# POWER_DCDC_SOM.net
KiCad netlist of a schematic drawn in Altium Designer
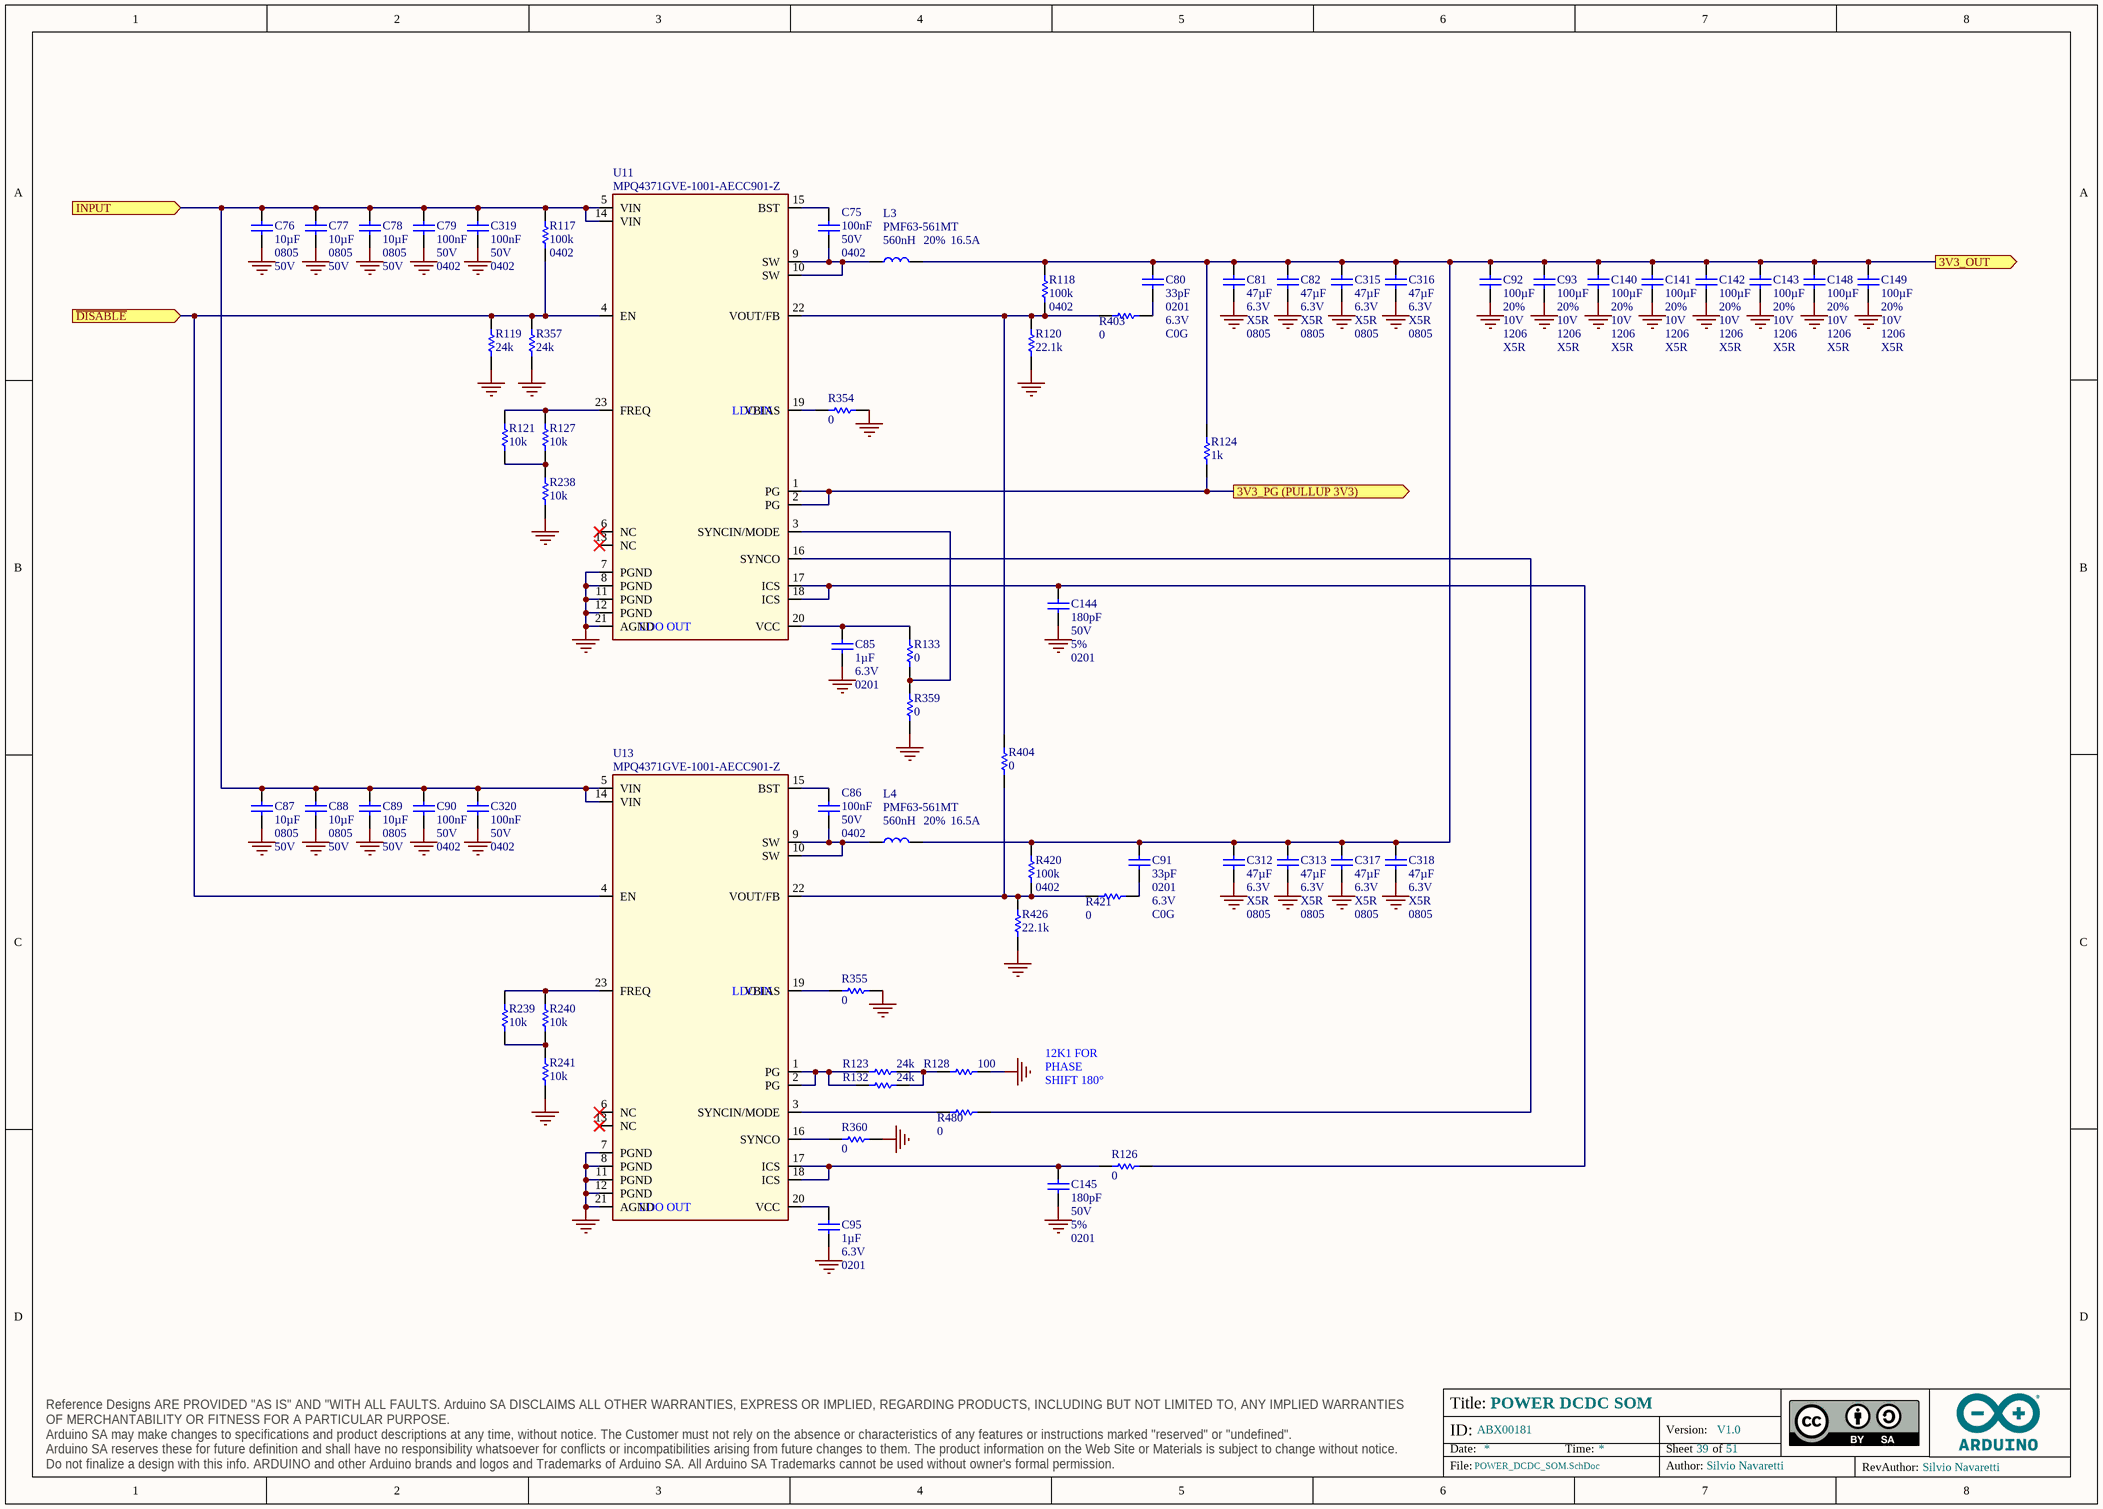
[diagram p0: POWER_DCDC_SOM.SchDoc]

(export (version "E")
  (design (tool "Eeschema 10.0.6"))
  (components
    (comp (ref "C75")
      (value "100nF")
      (footprint "CAP-0402")
      (description "CAP CHIP 0402 100nF 10% 50V X5R")
      (fields
        (field (name "MANUFACTURER") "Murata")
        (field (name "PART NUMBER") "GRM155R61H104KE19D")
        (field (name "VOLTAGE") "50V")
        (field (name "CASE CODE (IMPERIAL)") "0402")
      )
      (libsource (lib "Clean") (part "CAP"))
    )
    (comp (ref "C76")
      (value "10µF")
      (footprint "CAP-0805")
      (description "CAP CHIP 0805 10uF 20% 50V X5R")
      (fields
        (field (name "CASE CODE (IMPERIAL)") "0805")
        (field (name "TOLERANCE") "20%")
        (field (name "PART NUMBER") "GRM21BR61H106ME43L")
        (field (name "VOLTAGE") "50V")
      )
      (libsource (lib "Clean") (part "CAP"))
    )
    (comp (ref "C77")
      (value "10µF")
      (footprint "CAP-0805")
      (description "CAP CHIP 0805 10uF 20% 50V X5R")
      (fields
        (field (name "CASE CODE (IMPERIAL)") "0805")
        (field (name "TOLERANCE") "20%")
        (field (name "PART NUMBER") "GRM21BR61H106ME43L")
        (field (name "VOLTAGE") "50V")
      )
      (libsource (lib "Clean") (part "CAP"))
    )
    (comp (ref "C78")
      (value "10µF")
      (footprint "CAP-0805")
      (description "CAP CHIP 0805 10uF 20% 50V X5R")
      (fields
        (field (name "CASE CODE (IMPERIAL)") "0805")
        (field (name "TOLERANCE") "20%")
        (field (name "PART NUMBER") "GRM21BR61H106ME43L")
        (field (name "VOLTAGE") "50V")
      )
      (libsource (lib "Clean") (part "CAP"))
    )
    (comp (ref "C79")
      (value "100nF")
      (footprint "CAP-0402")
      (description "CAP CHIP 0402 100nF 10% 50V X5R")
      (fields
        (field (name "MANUFACTURER") "Murata")
        (field (name "PART NUMBER") "GRM155R61H104KE19D")
        (field (name "VOLTAGE") "50V")
        (field (name "CASE CODE (IMPERIAL)") "0402")
      )
      (libsource (lib "Clean") (part "CAP"))
    )
    (comp (ref "C80")
      (value "33pF")
      (footprint "CAP-0201")
      (description "CAP CHIP 0201 33pF 5% 6.3V C0G")
      (fields
        (field (name "CASE CODE (IMPERIAL)") "0201")
        (field (name "VOLTAGE") "6.3V")
        (field (name "MANUFACTURER") "Murata Electronics")
        (field (name "DIELECTRIC") "C0G")
        (field (name "TOLERANCE") "5%")
      )
      (libsource (lib "Clean") (part "CAP"))
    )
    (comp (ref "C81")
      (value "47µF")
      (footprint "CAP-0805")
      (description "CAP CHIP 0805 47uF 20% 6.3V X5R")
      (fields
        (field (name "VOLTAGE") "6.3V")
        (field (name "DIELECTRIC") "X5R")
        (field (name "TOLERANCE") "20%")
        (field (name "CASE CODE (IMPERIAL)") "0805")
        (field (name "MANUFACTURER") "KEMET")
      )
      (libsource (lib "Clean") (part "CAP"))
    )
    (comp (ref "C82")
      (value "47µF")
      (footprint "CAP-0805")
      (description "CAP CHIP 0805 47uF 20% 6.3V X5R")
      (fields
        (field (name "VOLTAGE") "6.3V")
        (field (name "DIELECTRIC") "X5R")
        (field (name "TOLERANCE") "20%")
        (field (name "CASE CODE (IMPERIAL)") "0805")
        (field (name "MANUFACTURER") "KEMET")
      )
      (libsource (lib "Clean") (part "CAP"))
    )
    (comp (ref "C85")
      (value "1µF")
      (footprint "CAP-0201")
      (description "CAP CHIP 0201 1uF 20% 6.3V X5R")
      (fields
        (field (name "VOLTAGE") "6.3V")
        (field (name "TOLERANCE") "20%")
        (field (name "PART NUMBER") "GRM033R60J105MEA2D")
        (field (name "CASE CODE (IMPERIAL)") "0201")
      )
      (libsource (lib "Clean") (part "CAP"))
    )
    (comp (ref "C86")
      (value "100nF")
      (footprint "CAP-0402")
      (description "CAP CHIP 0402 100nF 10% 50V X5R")
      (fields
        (field (name "MANUFACTURER") "Murata")
        (field (name "PART NUMBER") "GRM155R61H104KE19D")
        (field (name "VOLTAGE") "50V")
        (field (name "CASE CODE (IMPERIAL)") "0402")
      )
      (libsource (lib "Clean") (part "CAP"))
    )
    (comp (ref "C87")
      (value "10µF")
      (footprint "CAP-0805")
      (description "CAP CHIP 0805 10uF 20% 50V X5R")
      (fields
        (field (name "CASE CODE (IMPERIAL)") "0805")
        (field (name "TOLERANCE") "20%")
        (field (name "PART NUMBER") "GRM21BR61H106ME43L")
        (field (name "VOLTAGE") "50V")
      )
      (libsource (lib "Clean") (part "CAP"))
    )
    (comp (ref "C88")
      (value "10µF")
      (footprint "CAP-0805")
      (description "CAP CHIP 0805 10uF 20% 50V X5R")
      (fields
        (field (name "CASE CODE (IMPERIAL)") "0805")
        (field (name "TOLERANCE") "20%")
        (field (name "PART NUMBER") "GRM21BR61H106ME43L")
        (field (name "VOLTAGE") "50V")
      )
      (libsource (lib "Clean") (part "CAP"))
    )
    (comp (ref "C89")
      (value "10µF")
      (footprint "CAP-0805")
      (description "CAP CHIP 0805 10uF 20% 50V X5R")
      (fields
        (field (name "CASE CODE (IMPERIAL)") "0805")
        (field (name "TOLERANCE") "20%")
        (field (name "PART NUMBER") "GRM21BR61H106ME43L")
        (field (name "VOLTAGE") "50V")
      )
      (libsource (lib "Clean") (part "CAP"))
    )
    (comp (ref "C90")
      (value "100nF")
      (footprint "CAP-0402")
      (description "CAP CHIP 0402 100nF 10% 50V X5R")
      (fields
        (field (name "MANUFACTURER") "Murata")
        (field (name "PART NUMBER") "GRM155R61H104KE19D")
        (field (name "VOLTAGE") "50V")
        (field (name "CASE CODE (IMPERIAL)") "0402")
      )
      (libsource (lib "Clean") (part "CAP"))
    )
    (comp (ref "C91")
      (value "33pF")
      (footprint "CAP-0201")
      (description "CAP CHIP 0201 33pF 5% 6.3V C0G")
      (fields
        (field (name "CASE CODE (IMPERIAL)") "0201")
        (field (name "VOLTAGE") "6.3V")
        (field (name "MANUFACTURER") "Murata Electronics")
        (field (name "DIELECTRIC") "C0G")
        (field (name "TOLERANCE") "5%")
      )
      (libsource (lib "Clean") (part "CAP"))
    )
    (comp (ref "C92")
      (value "100µF")
      (footprint "CAP-1206")
      (description "CAP CHIP 1206 100uF 20% 10V X5R")
      (fields
        (field (name "TOLERANCE") "20%")
        (field (name "MANUFACTURER") "Murata")
        (field (name "VOLTAGE") "10V")
        (field (name "CASE CODE (IMPERIAL)") "1206")
        (field (name "DIELECTRIC") "X5R")
        (field (name "PART NUMBER") "GRM31CR61A107MEA8L")
      )
      (libsource (lib "Clean") (part "CAP"))
    )
    (comp (ref "C93")
      (value "100µF")
      (footprint "CAP-1206")
      (description "CAP CHIP 1206 100uF 20% 10V X5R")
      (fields
        (field (name "TOLERANCE") "20%")
        (field (name "MANUFACTURER") "Murata")
        (field (name "VOLTAGE") "10V")
        (field (name "CASE CODE (IMPERIAL)") "1206")
        (field (name "DIELECTRIC") "X5R")
        (field (name "PART NUMBER") "GRM31CR61A107MEA8L")
      )
      (libsource (lib "Clean") (part "CAP"))
    )
    (comp (ref "C95")
      (value "1µF")
      (footprint "CAP-0201")
      (description "CAP CHIP 0201 1uF 20% 6.3V X5R")
      (fields
        (field (name "VOLTAGE") "6.3V")
        (field (name "TOLERANCE") "20%")
        (field (name "PART NUMBER") "GRM033R60J105MEA2D")
        (field (name "CASE CODE (IMPERIAL)") "0201")
      )
      (libsource (lib "Clean") (part "CAP"))
    )
    (comp (ref "C140")
      (value "100µF")
      (footprint "CAP-1206")
      (description "CAP CHIP 1206 100uF 20% 10V X5R")
      (fields
        (field (name "TOLERANCE") "20%")
        (field (name "MANUFACTURER") "Murata")
        (field (name "VOLTAGE") "10V")
        (field (name "CASE CODE (IMPERIAL)") "1206")
        (field (name "DIELECTRIC") "X5R")
        (field (name "PART NUMBER") "GRM31CR61A107MEA8L")
      )
      (libsource (lib "Clean") (part "CAP"))
    )
    (comp (ref "C141")
      (value "100µF")
      (footprint "CAP-1206")
      (description "CAP CHIP 1206 100uF 20% 10V X5R")
      (fields
        (field (name "TOLERANCE") "20%")
        (field (name "MANUFACTURER") "Murata")
        (field (name "VOLTAGE") "10V")
        (field (name "CASE CODE (IMPERIAL)") "1206")
        (field (name "DIELECTRIC") "X5R")
        (field (name "PART NUMBER") "GRM31CR61A107MEA8L")
      )
      (libsource (lib "Clean") (part "CAP"))
    )
    (comp (ref "C142")
      (value "100µF")
      (footprint "CAP-1206")
      (description "CAP CHIP 1206 100uF 20% 10V X5R")
      (fields
        (field (name "TOLERANCE") "20%")
        (field (name "MANUFACTURER") "Murata")
        (field (name "VOLTAGE") "10V")
        (field (name "CASE CODE (IMPERIAL)") "1206")
        (field (name "DIELECTRIC") "X5R")
        (field (name "PART NUMBER") "GRM31CR61A107MEA8L")
      )
      (libsource (lib "Clean") (part "CAP"))
    )
    (comp (ref "C143")
      (value "100µF")
      (footprint "CAP-1206")
      (description "CAP CHIP 1206 100uF 20% 10V X5R")
      (fields
        (field (name "TOLERANCE") "20%")
        (field (name "MANUFACTURER") "Murata")
        (field (name "VOLTAGE") "10V")
        (field (name "CASE CODE (IMPERIAL)") "1206")
        (field (name "DIELECTRIC") "X5R")
        (field (name "PART NUMBER") "GRM31CR61A107MEA8L")
      )
      (libsource (lib "Clean") (part "CAP"))
    )
    (comp (ref "C144")
      (value "180pF")
      (footprint "CAP-0201")
      (description "CAP CHIP 0201 180pF 5% 50V C0G")
      (fields
        (field (name "MANUFACTURER") "Murata")
        (field (name "VOLTAGE") "50V")
        (field (name "TOLERANCE") "5%")
        (field (name "CASE CODE (IMPERIAL)") "0201")
        (field (name "PART NUMBER") "GRM0335C1H181JA01D")
      )
      (libsource (lib "Clean") (part "CAP"))
    )
    (comp (ref "C145")
      (value "180pF")
      (footprint "CAP-0201")
      (description "CAP CHIP 0201 180pF 5% 50V C0G")
      (fields
        (field (name "MANUFACTURER") "Murata")
        (field (name "VOLTAGE") "50V")
        (field (name "TOLERANCE") "5%")
        (field (name "CASE CODE (IMPERIAL)") "0201")
        (field (name "PART NUMBER") "GRM0335C1H181JA01D")
      )
      (libsource (lib "Clean") (part "CAP"))
    )
    (comp (ref "C148")
      (value "100µF")
      (footprint "CAP-1206")
      (description "CAP CHIP 1206 100uF 20% 10V X5R")
      (fields
        (field (name "TOLERANCE") "20%")
        (field (name "MANUFACTURER") "Murata")
        (field (name "VOLTAGE") "10V")
        (field (name "CASE CODE (IMPERIAL)") "1206")
        (field (name "DIELECTRIC") "X5R")
        (field (name "PART NUMBER") "GRM31CR61A107MEA8L")
      )
      (libsource (lib "Clean") (part "CAP"))
    )
    (comp (ref "C149")
      (value "100µF")
      (footprint "CAP-1206")
      (description "CAP CHIP 1206 100uF 20% 10V X5R")
      (fields
        (field (name "TOLERANCE") "20%")
        (field (name "MANUFACTURER") "Murata")
        (field (name "VOLTAGE") "10V")
        (field (name "CASE CODE (IMPERIAL)") "1206")
        (field (name "DIELECTRIC") "X5R")
        (field (name "PART NUMBER") "GRM31CR61A107MEA8L")
      )
      (libsource (lib "Clean") (part "CAP"))
    )
    (comp (ref "C312")
      (value "47µF")
      (footprint "CAP-0805")
      (description "CAP CHIP 0805 47uF 20% 6.3V X5R")
      (fields
        (field (name "VOLTAGE") "6.3V")
        (field (name "DIELECTRIC") "X5R")
        (field (name "TOLERANCE") "20%")
        (field (name "CASE CODE (IMPERIAL)") "0805")
        (field (name "MANUFACTURER") "KEMET")
      )
      (libsource (lib "Clean") (part "CAP"))
    )
    (comp (ref "C313")
      (value "47µF")
      (footprint "CAP-0805")
      (description "CAP CHIP 0805 47uF 20% 6.3V X5R")
      (fields
        (field (name "VOLTAGE") "6.3V")
        (field (name "DIELECTRIC") "X5R")
        (field (name "TOLERANCE") "20%")
        (field (name "CASE CODE (IMPERIAL)") "0805")
        (field (name "MANUFACTURER") "KEMET")
      )
      (libsource (lib "Clean") (part "CAP"))
    )
    (comp (ref "C315")
      (value "47µF")
      (footprint "CAP-0805")
      (description "CAP CHIP 0805 47uF 20% 6.3V X5R")
      (fields
        (field (name "VOLTAGE") "6.3V")
        (field (name "DIELECTRIC") "X5R")
        (field (name "TOLERANCE") "20%")
        (field (name "CASE CODE (IMPERIAL)") "0805")
        (field (name "MANUFACTURER") "KEMET")
      )
      (libsource (lib "Clean") (part "CAP"))
    )
    (comp (ref "C316")
      (value "47µF")
      (footprint "CAP-0805")
      (description "CAP CHIP 0805 47uF 20% 6.3V X5R")
      (fields
        (field (name "VOLTAGE") "6.3V")
        (field (name "DIELECTRIC") "X5R")
        (field (name "TOLERANCE") "20%")
        (field (name "CASE CODE (IMPERIAL)") "0805")
        (field (name "MANUFACTURER") "KEMET")
      )
      (libsource (lib "Clean") (part "CAP"))
    )
    (comp (ref "C317")
      (value "47µF")
      (footprint "CAP-0805")
      (description "CAP CHIP 0805 47uF 20% 6.3V X5R")
      (fields
        (field (name "VOLTAGE") "6.3V")
        (field (name "DIELECTRIC") "X5R")
        (field (name "TOLERANCE") "20%")
        (field (name "CASE CODE (IMPERIAL)") "0805")
        (field (name "MANUFACTURER") "KEMET")
      )
      (libsource (lib "Clean") (part "CAP"))
    )
    (comp (ref "C318")
      (value "47µF")
      (footprint "CAP-0805")
      (description "CAP CHIP 0805 47uF 20% 6.3V X5R")
      (fields
        (field (name "VOLTAGE") "6.3V")
        (field (name "DIELECTRIC") "X5R")
        (field (name "TOLERANCE") "20%")
        (field (name "CASE CODE (IMPERIAL)") "0805")
        (field (name "MANUFACTURER") "KEMET")
      )
      (libsource (lib "Clean") (part "CAP"))
    )
    (comp (ref "C319")
      (value "100nF")
      (footprint "CAP-0402")
      (description "CAP CHIP 0402 100nF 10% 50V X5R")
      (fields
        (field (name "MANUFACTURER") "Murata")
        (field (name "PART NUMBER") "GRM155R61H104KE19D")
        (field (name "VOLTAGE") "50V")
        (field (name "CASE CODE (IMPERIAL)") "0402")
      )
      (libsource (lib "Clean") (part "CAP"))
    )
    (comp (ref "C320")
      (value "100nF")
      (footprint "CAP-0402")
      (description "CAP CHIP 0402 100nF 10% 50V X5R")
      (fields
        (field (name "MANUFACTURER") "Murata")
        (field (name "PART NUMBER") "GRM155R61H104KE19D")
        (field (name "VOLTAGE") "50V")
        (field (name "CASE CODE (IMPERIAL)") "0402")
      )
      (libsource (lib "Clean") (part "CAP"))
    )
    (comp (ref "L3")
      (value "PMF63-561MT")
      (footprint "PMF63")
      (description "IND 0.56uH 20%, max 5mR, IRMS 16.5A, Isat 25.5A, 7.3x6.6x3mm")
      (fields
        (field (name "INDUCTANCE") "560nH")
        (field (name "IRMS") "16.5A")
        (field (name "TOLERANCE") "20%")
        (field (name "MANUFACTURER") "K-WELL")
      )
      (libsource (lib "Clean") (part "DNP IND CHIP 0201"))
    )
    (comp (ref "L4")
      (value "PMF63-561MT")
      (footprint "PMF63")
      (description "IND 0.56uH 20%, max 5mR, IRMS 16.5A, Isat 25.5A, 7.3x6.6x3mm")
      (fields
        (field (name "INDUCTANCE") "560nH")
        (field (name "IRMS") "16.5A")
        (field (name "TOLERANCE") "20%")
        (field (name "MANUFACTURER") "K-WELL")
      )
      (libsource (lib "Clean") (part "DNP IND CHIP 0201"))
    )
    (comp (ref "R117")
      (value "100k")
      (footprint "RES-0402")
      (description "RES CHIP 0402 100k 1% 1/16W")
      (fields
        (field (name "POWER") "62.5mW")
        (field (name "TOLERANCE") "1%")
        (field (name "CASE CODE (IMPERIAL)") "0402")
      )
      (libsource (lib "Clean") (part "RES"))
    )
    (comp (ref "R118")
      (value "100k")
      (footprint "RES-0402")
      (description "RES CHIP 0402 100k 1% 1/16W")
      (fields
        (field (name "POWER") "62.5mW")
        (field (name "TOLERANCE") "1%")
        (field (name "CASE CODE (IMPERIAL)") "0402")
      )
      (libsource (lib "Clean") (part "RES"))
    )
    (comp (ref "R119")
      (value "24k")
      (footprint "RES-0201")
      (description "RES CHIP 0201 24k 1% 1/20W")
      (fields (field (name "POWER") "50mW") (field (name "TOLERANCE") "1%"))
      (libsource (lib "Clean") (part "RES"))
    )
    (comp (ref "R120")
      (value "22.1k")
      (footprint "RES-0201")
      (description "RES CHIP 0201 22k1 1% 1/20W")
      (fields (field (name "PART NUMBER") "RC0201FR-0722K1L") (field (name "MANUFACTURER") "YAGEO"))
      (libsource (lib "Clean") (part "RES"))
    )
    (comp (ref "R121")
      (value "10k")
      (footprint "RES-0201")
      (description "RES CHIP 0201 10k 1% 1/20W")
      (fields (field (name "POWER") "50mW") (field (name "TOLERANCE") "1%"))
      (libsource (lib "Clean") (part "RES"))
    )
    (comp (ref "R123")
      (value "24k")
      (footprint "RES-0201")
      (description "RES CHIP 0201 24k 1% 1/20W")
      (fields (field (name "POWER") "50mW") (field (name "PART NUMBER") "RC0201FR-0724KL"))
      (libsource (lib "Clean") (part "RES"))
    )
    (comp (ref "R124")
      (value "1k")
      (footprint "RES-0201")
      (description "RES CHIP 0201 1k 1% 1/20W")
      (fields (field (name "POWER") "50mW") (field (name "TOLERANCE") "1%"))
      (libsource (lib "Clean") (part "RES"))
    )
    (comp (ref "R126")
      (value "0")
      (footprint "RES-0201")
      (description "RES CHIP 0201 0R")
      (fields (field (name "MANUFACTURER") "Vishay") (field (name "PART NUMBER") "CRCW02010000Z0ED"))
      (libsource (lib "Clean") (part "RES"))
    )
    (comp (ref "R127")
      (value "10k")
      (footprint "RES-0201")
      (description "RES CHIP 0201 10k 1% 1/20W")
      (fields (field (name "POWER") "50mW") (field (name "TOLERANCE") "1%"))
      (libsource (lib "Clean") (part "RES"))
    )
    (comp (ref "R128")
      (value "100")
      (footprint "RES-0201")
      (description "RES CHIP 0201 100R 1% 1/20W")
      (fields (field (name "POWER") "50mW") (field (name "TOLERANCE") "1%"))
      (libsource (lib "Clean") (part "RES"))
    )
    (comp (ref "R132")
      (value "24k")
      (footprint "RES-0201")
      (description "RES CHIP 0201 24k 1% 1/20W")
      (fields (field (name "POWER") "50mW") (field (name "PART NUMBER") "RC0201FR-0724KL"))
      (libsource (lib "Clean") (part "RES"))
    )
    (comp (ref "R133")
      (value "0")
      (footprint "RES-0201")
      (description "RES CHIP 0201 0R")
      (fields (field (name "MANUFACTURER") "Vishay") (field (name "PART NUMBER") "CRCW02010000Z0ED"))
      (libsource (lib "Clean") (part "RES"))
    )
    (comp (ref "R238")
      (value "10k")
      (footprint "RES-0201")
      (description "RES CHIP 0201 10k 1% 1/20W")
      (fields (field (name "POWER") "50mW") (field (name "TOLERANCE") "1%"))
      (libsource (lib "Clean") (part "RES"))
    )
    (comp (ref "R239")
      (value "10k")
      (footprint "RES-0201")
      (description "RES CHIP 0201 10k 1% 1/20W")
      (fields (field (name "POWER") "50mW") (field (name "TOLERANCE") "1%"))
      (libsource (lib "Clean") (part "RES"))
    )
    (comp (ref "R240")
      (value "10k")
      (footprint "RES-0201")
      (description "RES CHIP 0201 10k 1% 1/20W")
      (fields (field (name "POWER") "50mW") (field (name "TOLERANCE") "1%"))
      (libsource (lib "Clean") (part "RES"))
    )
    (comp (ref "R241")
      (value "10k")
      (footprint "RES-0201")
      (description "RES CHIP 0201 10k 1% 1/20W")
      (fields (field (name "POWER") "50mW") (field (name "TOLERANCE") "1%"))
      (libsource (lib "Clean") (part "RES"))
    )
    (comp (ref "R354")
      (value "0")
      (footprint "RES-0201")
      (description "RES CHIP 0201 0R")
      (fields (field (name "MANUFACTURER") "Vishay") (field (name "PART NUMBER") "CRCW02010000Z0ED"))
      (libsource (lib "Clean") (part "RES"))
    )
    (comp (ref "R355")
      (value "0")
      (footprint "RES-0201")
      (description "RES CHIP 0201 0R")
      (fields (field (name "MANUFACTURER") "Vishay") (field (name "PART NUMBER") "CRCW02010000Z0ED"))
      (libsource (lib "Clean") (part "RES"))
    )
    (comp (ref "R357")
      (value "24k")
      (footprint "RES-0201")
      (description "RES CHIP 0201 24k 1% 1/20W")
      (fields (field (name "POWER") "50mW") (field (name "TOLERANCE") "1%"))
      (libsource (lib "Clean") (part "RES"))
    )
    (comp (ref "R359")
      (value "0")
      (footprint "RES-0201")
      (description "RES CHIP 0201 0R")
      (fields (field (name "MANUFACTURER") "Vishay") (field (name "PART NUMBER") "CRCW02010000Z0ED"))
      (libsource (lib "Clean") (part "RES"))
    )
    (comp (ref "R360")
      (value "0")
      (footprint "RES-0201")
      (description "RES CHIP 0201 0R")
      (fields (field (name "MANUFACTURER") "Vishay") (field (name "PART NUMBER") "CRCW02010000Z0ED"))
      (libsource (lib "Clean") (part "RES"))
    )
    (comp (ref "R403")
      (value "0")
      (footprint "RES-0201")
      (description "RES CHIP 0201 0R")
      (fields (field (name "MANUFACTURER") "Vishay") (field (name "PART NUMBER") "CRCW02010000Z0ED"))
      (libsource (lib "Clean") (part "RES"))
    )
    (comp (ref "R404")
      (value "0")
      (footprint "RES-0201")
      (description "RES CHIP 0201 0R")
      (fields (field (name "MANUFACTURER") "Vishay") (field (name "PART NUMBER") "CRCW02010000Z0ED"))
      (libsource (lib "Clean") (part "RES"))
    )
    (comp (ref "R420")
      (value "100k")
      (footprint "RES-0402")
      (description "RES CHIP 0402 100k 1% 1/16W")
      (fields
        (field (name "POWER") "62.5mW")
        (field (name "TOLERANCE") "1%")
        (field (name "CASE CODE (IMPERIAL)") "0402")
      )
      (libsource (lib "Clean") (part "RES"))
    )
    (comp (ref "R421")
      (value "0")
      (footprint "RES-0201")
      (description "RES CHIP 0201 0R")
      (fields (field (name "MANUFACTURER") "Vishay") (field (name "PART NUMBER") "CRCW02010000Z0ED"))
      (libsource (lib "Clean") (part "RES"))
    )
    (comp (ref "R426")
      (value "22.1k")
      (footprint "RES-0201")
      (description "RES CHIP 0201 22k1 1% 1/20W")
      (fields (field (name "PART NUMBER") "RC0201FR-0722K1L") (field (name "MANUFACTURER") "YAGEO"))
      (libsource (lib "Clean") (part "RES"))
    )
    (comp (ref "R480")
      (value "0")
      (footprint "RES-0201")
      (description "RES CHIP 0201 0R")
      (fields (field (name "MANUFACTURER") "Vishay") (field (name "PART NUMBER") "CRCW02010000Z0ED"))
      (libsource (lib "Clean") (part "RES"))
    )
    (comp (ref "U11")
      (value "MPQ4371GVE-1001-AECC901-Z")
      (footprint "MPQ4371GVE-1001-AECC901-Z")
      (description "IC Buck Vin 36V, Vout ADJ, Iout max 11A, with FSS, multi phase, QFN23 4x5mm")
      (fields (field (name "MANUFACTURER") "MPS"))
      (libsource (lib "Clean") (part "MPQ4371GVE-1001-AECC901-Z-Symbol-1"))
    )
    (comp (ref "U13")
      (value "MPQ4371GVE-1001-AECC901-Z")
      (footprint "MPQ4371GVE-1001-AECC901-Z")
      (description "IC Buck Vin 36V, Vout ADJ, Iout max 11A, with FSS, multi phase, QFN23 4x5mm")
      (fields (field (name "MANUFACTURER") "MPS"))
      (libsource (lib "Clean") (part "MPQ4371GVE-1001-AECC901-Z-Symbol-1"))
    )
  )
  (nets
    (net (code "1") (name "/3V3_OUT") (class "Default")
      (node (ref "C140") (pin "1") (pinfunction "1_1") (pintype "passive"))
      (node (ref "C141") (pin "1") (pinfunction "1_1") (pintype "passive"))
      (node (ref "C142") (pin "1") (pinfunction "1_1") (pintype "passive"))
      (node (ref "C143") (pin "1") (pinfunction "1_1") (pintype "passive"))
      (node (ref "C148") (pin "1") (pinfunction "1_1") (pintype "passive"))
      (node (ref "C149") (pin "1") (pinfunction "1_1") (pintype "passive"))
      (node (ref "C312") (pin "2") (pinfunction "2_2") (pintype "passive"))
      (node (ref "C313") (pin "2") (pinfunction "2_2") (pintype "passive"))
      (node (ref "C315") (pin "2") (pinfunction "2_2") (pintype "passive"))
      (node (ref "C316") (pin "2") (pinfunction "2_2") (pintype "passive"))
      (node (ref "C317") (pin "2") (pinfunction "2_2") (pintype "passive"))
      (node (ref "C318") (pin "2") (pinfunction "2_2") (pintype "passive"))
      (node (ref "C80") (pin "2") (pinfunction "2_2") (pintype "passive"))
      (node (ref "C81") (pin "2") (pinfunction "2_2") (pintype "passive"))
      (node (ref "C82") (pin "2") (pinfunction "2_2") (pintype "passive"))
      (node (ref "C91") (pin "2") (pinfunction "2_2") (pintype "passive"))
      (node (ref "C92") (pin "1") (pinfunction "1_1") (pintype "passive"))
      (node (ref "C93") (pin "1") (pinfunction "1_1") (pintype "passive"))
      (node (ref "L3") (pin "2") (pinfunction "2_2") (pintype "passive"))
      (node (ref "L4") (pin "2") (pinfunction "2_2") (pintype "passive"))
      (node (ref "R118") (pin "1") (pinfunction "1_1") (pintype "passive"))
      (node (ref "R124") (pin "1") (pinfunction "1_1") (pintype "passive"))
      (node (ref "R420") (pin "1") (pinfunction "1_1") (pintype "passive"))
    )
    (net (code "2") (name "/3V3_PG (PULLUP 3V3)") (class "Default")
      (node (ref "R124") (pin "2") (pinfunction "2_2") (pintype "passive"))
      (node (ref "U11") (pin "1") (pinfunction "PG_1") (pintype "passive"))
      (node (ref "U11") (pin "2") (pinfunction "PG_2") (pintype "passive"))
    )
    (net (code "3") (name "/INPUT") (class "Default")
      (node (ref "C319") (pin "1") (pinfunction "1_1") (pintype "passive"))
      (node (ref "C320") (pin "1") (pinfunction "1_1") (pintype "passive"))
      (node (ref "C76") (pin "1") (pinfunction "1_1") (pintype "passive"))
      (node (ref "C77") (pin "1") (pinfunction "1_1") (pintype "passive"))
      (node (ref "C78") (pin "1") (pinfunction "1_1") (pintype "passive"))
      (node (ref "C79") (pin "1") (pinfunction "1_1") (pintype "passive"))
      (node (ref "C87") (pin "1") (pinfunction "1_1") (pintype "passive"))
      (node (ref "C88") (pin "1") (pinfunction "1_1") (pintype "passive"))
      (node (ref "C89") (pin "1") (pinfunction "1_1") (pintype "passive"))
      (node (ref "C90") (pin "1") (pinfunction "1_1") (pintype "passive"))
      (node (ref "R117") (pin "1") (pinfunction "1_1") (pintype "passive"))
      (node (ref "U11") (pin "14") (pinfunction "VIN_14") (pintype "passive"))
      (node (ref "U11") (pin "5") (pinfunction "VIN_5") (pintype "passive"))
      (node (ref "U13") (pin "14") (pinfunction "VIN_14") (pintype "passive"))
      (node (ref "U13") (pin "5") (pinfunction "VIN_5") (pintype "passive"))
    )
    (net (code "4") (name "/~{DISABLE}") (class "Default")
      (node (ref "R117") (pin "2") (pinfunction "2_2") (pintype "passive"))
      (node (ref "R119") (pin "2") (pinfunction "2_2") (pintype "passive"))
      (node (ref "R357") (pin "2") (pinfunction "2_2") (pintype "passive"))
      (node (ref "U11") (pin "4") (pinfunction "EN_4") (pintype "passive"))
      (node (ref "U13") (pin "4") (pinfunction "EN_4") (pintype "passive"))
    )
    (net (code "5") (name "GND") (class "Default")
      (node (ref "C140") (pin "2") (pinfunction "2_2") (pintype "passive"))
      (node (ref "C141") (pin "2") (pinfunction "2_2") (pintype "passive"))
      (node (ref "C142") (pin "2") (pinfunction "2_2") (pintype "passive"))
      (node (ref "C143") (pin "2") (pinfunction "2_2") (pintype "passive"))
      (node (ref "C144") (pin "1") (pinfunction "1_1") (pintype "passive"))
      (node (ref "C145") (pin "1") (pinfunction "1_1") (pintype "passive"))
      (node (ref "C148") (pin "2") (pinfunction "2_2") (pintype "passive"))
      (node (ref "C149") (pin "2") (pinfunction "2_2") (pintype "passive"))
      (node (ref "C312") (pin "1") (pinfunction "1_1") (pintype "passive"))
      (node (ref "C313") (pin "1") (pinfunction "1_1") (pintype "passive"))
      (node (ref "C315") (pin "1") (pinfunction "1_1") (pintype "passive"))
      (node (ref "C316") (pin "1") (pinfunction "1_1") (pintype "passive"))
      (node (ref "C317") (pin "1") (pinfunction "1_1") (pintype "passive"))
      (node (ref "C318") (pin "1") (pinfunction "1_1") (pintype "passive"))
      (node (ref "C319") (pin "2") (pinfunction "2_2") (pintype "passive"))
      (node (ref "C320") (pin "2") (pinfunction "2_2") (pintype "passive"))
      (node (ref "C76") (pin "2") (pinfunction "2_2") (pintype "passive"))
      (node (ref "C77") (pin "2") (pinfunction "2_2") (pintype "passive"))
      (node (ref "C78") (pin "2") (pinfunction "2_2") (pintype "passive"))
      (node (ref "C79") (pin "2") (pinfunction "2_2") (pintype "passive"))
      (node (ref "C81") (pin "1") (pinfunction "1_1") (pintype "passive"))
      (node (ref "C82") (pin "1") (pinfunction "1_1") (pintype "passive"))
      (node (ref "C85") (pin "1") (pinfunction "1_1") (pintype "passive"))
      (node (ref "C87") (pin "2") (pinfunction "2_2") (pintype "passive"))
      (node (ref "C88") (pin "2") (pinfunction "2_2") (pintype "passive"))
      (node (ref "C89") (pin "2") (pinfunction "2_2") (pintype "passive"))
      (node (ref "C90") (pin "2") (pinfunction "2_2") (pintype "passive"))
      (node (ref "C92") (pin "2") (pinfunction "2_2") (pintype "passive"))
      (node (ref "C93") (pin "2") (pinfunction "2_2") (pintype "passive"))
      (node (ref "C95") (pin "1") (pinfunction "1_1") (pintype "passive"))
      (node (ref "R119") (pin "1") (pinfunction "1_1") (pintype "passive"))
      (node (ref "R120") (pin "1") (pinfunction "1_1") (pintype "passive"))
      (node (ref "R128") (pin "2") (pinfunction "2_2") (pintype "passive"))
      (node (ref "R238") (pin "1") (pinfunction "1_1") (pintype "passive"))
      (node (ref "R241") (pin "1") (pinfunction "1_1") (pintype "passive"))
      (node (ref "R354") (pin "1") (pinfunction "1_1") (pintype "passive"))
      (node (ref "R355") (pin "1") (pinfunction "1_1") (pintype "passive"))
      (node (ref "R357") (pin "1") (pinfunction "1_1") (pintype "passive"))
      (node (ref "R359") (pin "1") (pinfunction "1_1") (pintype "passive"))
      (node (ref "R360") (pin "1") (pinfunction "1_1") (pintype "passive"))
      (node (ref "R426") (pin "1") (pinfunction "1_1") (pintype "passive"))
      (node (ref "U11") (pin "11") (pinfunction "PGND_11") (pintype "passive"))
      (node (ref "U11") (pin "12") (pinfunction "PGND_12") (pintype "passive"))
      (node (ref "U11") (pin "21") (pinfunction "AGND_21") (pintype "passive"))
      (node (ref "U11") (pin "7") (pinfunction "PGND_7") (pintype "passive"))
      (node (ref "U11") (pin "8") (pinfunction "PGND_8") (pintype "passive"))
      (node (ref "U13") (pin "11") (pinfunction "PGND_11") (pintype "passive"))
      (node (ref "U13") (pin "12") (pinfunction "PGND_12") (pintype "passive"))
      (node (ref "U13") (pin "21") (pinfunction "AGND_21") (pintype "passive"))
      (node (ref "U13") (pin "7") (pinfunction "PGND_7") (pintype "passive"))
      (node (ref "U13") (pin "8") (pinfunction "PGND_8") (pintype "passive"))
    )
    (net (code "6") (name "Net-(C75-Pad2)") (class "Default")
      (node (ref "C75") (pin "2") (pinfunction "2_2") (pintype "passive"))
      (node (ref "L3") (pin "1") (pinfunction "1_1") (pintype "passive"))
      (node (ref "U11") (pin "10") (pinfunction "SW_10") (pintype "passive"))
      (node (ref "U11") (pin "9") (pinfunction "SW_9") (pintype "passive"))
    )
    (net (code "7") (name "Net-(C80-Pad1)") (class "Default")
      (node (ref "C80") (pin "1") (pinfunction "1_1") (pintype "passive"))
      (node (ref "R403") (pin "2") (pinfunction "2_2") (pintype "passive"))
    )
    (net (code "8") (name "Net-(C86-Pad2)") (class "Default")
      (node (ref "C86") (pin "2") (pinfunction "2_2") (pintype "passive"))
      (node (ref "L4") (pin "1") (pinfunction "1_1") (pintype "passive"))
      (node (ref "U13") (pin "10") (pinfunction "SW_10") (pintype "passive"))
      (node (ref "U13") (pin "9") (pinfunction "SW_9") (pintype "passive"))
    )
    (net (code "9") (name "Net-(C91-Pad1)") (class "Default")
      (node (ref "C91") (pin "1") (pinfunction "1_1") (pintype "passive"))
      (node (ref "R421") (pin "2") (pinfunction "2_2") (pintype "passive"))
    )
    (net (code "10") (name "Net-(C144-Pad2)") (class "Default")
      (node (ref "C144") (pin "2") (pinfunction "2_2") (pintype "passive"))
      (node (ref "R126") (pin "1") (pinfunction "1_1") (pintype "passive"))
      (node (ref "U11") (pin "17") (pinfunction "ICS_17") (pintype "passive"))
      (node (ref "U11") (pin "18") (pinfunction "ICS_18") (pintype "passive"))
    )
    (net (code "11") (name "Net-(C145-Pad2)") (class "Default")
      (node (ref "C145") (pin "2") (pinfunction "2_2") (pintype "passive"))
      (node (ref "R126") (pin "2") (pinfunction "2_2") (pintype "passive"))
      (node (ref "U13") (pin "17") (pinfunction "ICS_17") (pintype "passive"))
      (node (ref "U13") (pin "18") (pinfunction "ICS_18") (pintype "passive"))
    )
    (net (code "12") (name "Net-(R121-Pad1)") (class "Default")
      (node (ref "R121") (pin "1") (pinfunction "1_1") (pintype "passive"))
      (node (ref "R127") (pin "1") (pinfunction "1_1") (pintype "passive"))
      (node (ref "R238") (pin "2") (pinfunction "2_2") (pintype "passive"))
    )
    (net (code "13") (name "Net-(R123-Pad1)") (class "Default")
      (node (ref "R123") (pin "1") (pinfunction "1_1") (pintype "passive"))
      (node (ref "R128") (pin "1") (pinfunction "1_1") (pintype "passive"))
      (node (ref "R132") (pin "1") (pinfunction "1_1") (pintype "passive"))
    )
    (net (code "14") (name "Net-(R123-Pad2)") (class "Default")
      (node (ref "R123") (pin "2") (pinfunction "2_2") (pintype "passive"))
      (node (ref "R132") (pin "2") (pinfunction "2_2") (pintype "passive"))
      (node (ref "U13") (pin "1") (pinfunction "PG_1") (pintype "passive"))
      (node (ref "U13") (pin "2") (pinfunction "PG_2") (pintype "passive"))
    )
    (net (code "15") (name "Net-(R239-Pad1)") (class "Default")
      (node (ref "R239") (pin "1") (pinfunction "1_1") (pintype "passive"))
      (node (ref "R240") (pin "1") (pinfunction "1_1") (pintype "passive"))
      (node (ref "R241") (pin "2") (pinfunction "2_2") (pintype "passive"))
    )
    (net (code "16") (name "Net-(U11-BST)") (class "Default")
      (node (ref "C75") (pin "1") (pinfunction "1_1") (pintype "passive"))
      (node (ref "U11") (pin "15") (pinfunction "BST_15") (pintype "passive"))
    )
    (net (code "17") (name "Net-(U11-FREQ)") (class "Default")
      (node (ref "R121") (pin "2") (pinfunction "2_2") (pintype "passive"))
      (node (ref "R127") (pin "2") (pinfunction "2_2") (pintype "passive"))
      (node (ref "U11") (pin "23") (pinfunction "FREQ_23") (pintype "passive"))
    )
    (net (code "18") (name "Net-(U11-SYNCIN{slash}MODE)") (class "Default")
      (node (ref "R133") (pin "1") (pinfunction "1_1") (pintype "passive"))
      (node (ref "R359") (pin "2") (pinfunction "2_2") (pintype "passive"))
      (node (ref "U11") (pin "3") (pinfunction "SYNCIN/MODE_3") (pintype "passive"))
    )
    (net (code "19") (name "Net-(U11-SYNCO)") (class "Default")
      (node (ref "R480") (pin "2") (pinfunction "2_2") (pintype "passive"))
      (node (ref "U11") (pin "16") (pinfunction "SYNCO_16") (pintype "passive"))
    )
    (net (code "20") (name "Net-(U11-VBIAS)") (class "Default")
      (node (ref "R354") (pin "2") (pinfunction "2_2") (pintype "passive"))
      (node (ref "U11") (pin "19") (pinfunction "VBIAS_19") (pintype "passive"))
    )
    (net (code "21") (name "Net-(U11-VCC)") (class "Default")
      (node (ref "C85") (pin "2") (pinfunction "2_2") (pintype "passive"))
      (node (ref "R133") (pin "2") (pinfunction "2_2") (pintype "passive"))
      (node (ref "U11") (pin "20") (pinfunction "VCC_20") (pintype "passive"))
    )
    (net (code "22") (name "Net-(U11-VOUT{slash}FB)") (class "Default")
      (node (ref "R118") (pin "2") (pinfunction "2_2") (pintype "passive"))
      (node (ref "R120") (pin "2") (pinfunction "2_2") (pintype "passive"))
      (node (ref "R403") (pin "1") (pinfunction "1_1") (pintype "passive"))
      (node (ref "R404") (pin "1") (pinfunction "1_1") (pintype "passive"))
      (node (ref "U11") (pin "22") (pinfunction "VOUT/FB_22") (pintype "passive"))
    )
    (net (code "23") (name "Net-(U13-BST)") (class "Default")
      (node (ref "C86") (pin "1") (pinfunction "1_1") (pintype "passive"))
      (node (ref "U13") (pin "15") (pinfunction "BST_15") (pintype "passive"))
    )
    (net (code "24") (name "Net-(U13-FREQ)") (class "Default")
      (node (ref "R239") (pin "2") (pinfunction "2_2") (pintype "passive"))
      (node (ref "R240") (pin "2") (pinfunction "2_2") (pintype "passive"))
      (node (ref "U13") (pin "23") (pinfunction "FREQ_23") (pintype "passive"))
    )
    (net (code "25") (name "Net-(U13-SYNCIN{slash}MODE)") (class "Default")
      (node (ref "R480") (pin "1") (pinfunction "1_1") (pintype "passive"))
      (node (ref "U13") (pin "3") (pinfunction "SYNCIN/MODE_3") (pintype "passive"))
    )
    (net (code "26") (name "Net-(U13-SYNCO)") (class "Default")
      (node (ref "R360") (pin "2") (pinfunction "2_2") (pintype "passive"))
      (node (ref "U13") (pin "16") (pinfunction "SYNCO_16") (pintype "passive"))
    )
    (net (code "27") (name "Net-(U13-VBIAS)") (class "Default")
      (node (ref "R355") (pin "2") (pinfunction "2_2") (pintype "passive"))
      (node (ref "U13") (pin "19") (pinfunction "VBIAS_19") (pintype "passive"))
    )
    (net (code "28") (name "Net-(U13-VCC)") (class "Default")
      (node (ref "C95") (pin "2") (pinfunction "2_2") (pintype "passive"))
      (node (ref "U13") (pin "20") (pinfunction "VCC_20") (pintype "passive"))
    )
    (net (code "29") (name "Net-(U13-VOUT{slash}FB)") (class "Default")
      (node (ref "R404") (pin "2") (pinfunction "2_2") (pintype "passive"))
      (node (ref "R420") (pin "2") (pinfunction "2_2") (pintype "passive"))
      (node (ref "R421") (pin "1") (pinfunction "1_1") (pintype "passive"))
      (node (ref "R426") (pin "2") (pinfunction "2_2") (pintype "passive"))
      (node (ref "U13") (pin "22") (pinfunction "VOUT/FB_22") (pintype "passive"))
    )
    (net (code "30") (name "unconnected-(U11-NC-Pad6)") (class "Default")
      (node (ref "U11") (pin "6") (pinfunction "NC_6") (pintype "passive+no_connect"))
    )
    (net (code "31") (name "unconnected-(U11-NC-Pad13)") (class "Default")
      (node (ref "U11") (pin "13") (pinfunction "NC_13") (pintype "passive+no_connect"))
    )
    (net (code "32") (name "unconnected-(U13-NC-Pad6)") (class "Default")
      (node (ref "U13") (pin "6") (pinfunction "NC_6") (pintype "passive+no_connect"))
    )
    (net (code "33") (name "unconnected-(U13-NC-Pad13)") (class "Default")
      (node (ref "U13") (pin "13") (pinfunction "NC_13") (pintype "passive+no_connect"))
    )
  )
)
